# CPU_PHY.net
KiCad netlist of a schematic drawn in Altium Designer
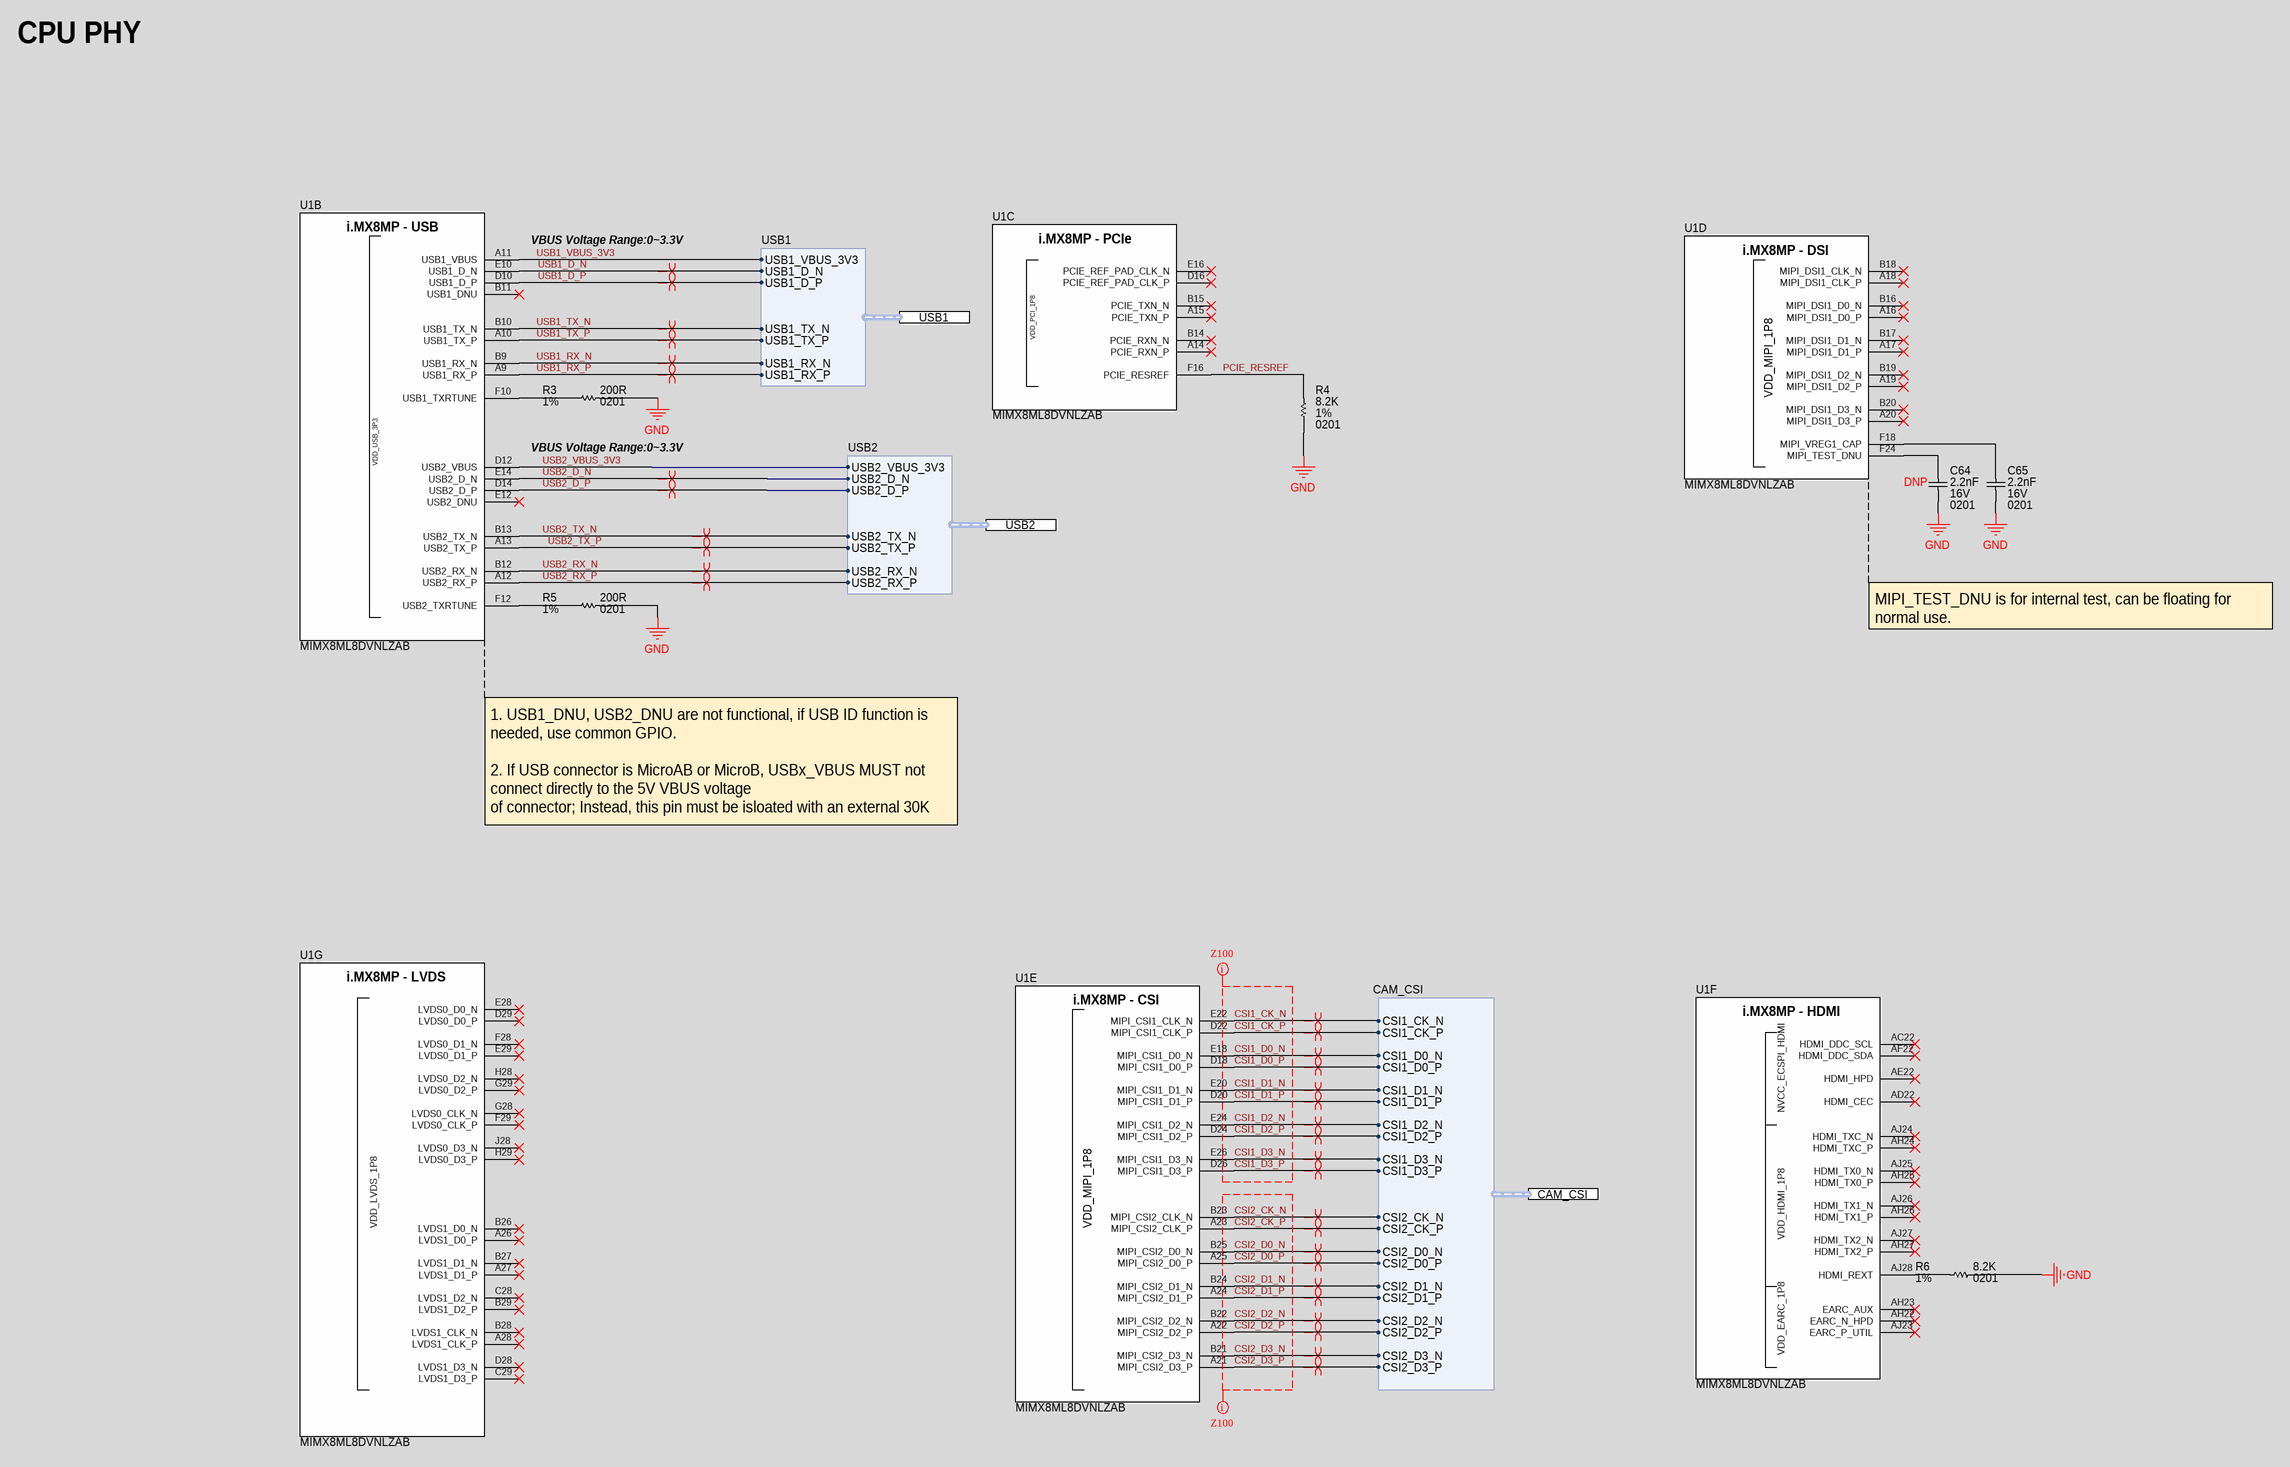
[diagram p0: CPU PHY.SchDoc]

(export (version "E")
  (design (tool "Eeschema 10.0.6"))
  (components
    (comp (ref "C64")
      (value "GRM033R71C222KA88D")
      (footprint "CAP_0201_CAPC0603X03N")
      (description "Multilayer Ceramic Capacitor, 2200 pF, 16 V, ± 10%, X7R, 0201 [0603 Metric]")
      (fields
        (field (name "MANUFACTURER") "Murata")
        (field (name "TOLERANCE") "10%")
        (field (name "VOLTAGE RATING") "16V")
        (field (name "CAPACITANCE") "2.2nF")
        (field (name "CASE/PACKAGE") "0201")
      )
      (libsource (lib "Electronic Devices_LIB") (part "CAP_2200pF_16V_X7R_0201"))
    )
    (comp (ref "C65")
      (value "GRM033R71C222KA88D")
      (footprint "CAP_0201_CAPC0603X03N")
      (description "Multilayer Ceramic Capacitor, 2200 pF, 16 V, ± 10%, X7R, 0201 [0603 Metric]")
      (fields
        (field (name "MANUFACTURER") "Murata")
        (field (name "TOLERANCE") "10%")
        (field (name "VOLTAGE RATING") "16V")
        (field (name "CAPACITANCE") "2.2nF")
        (field (name "CASE/PACKAGE") "0201")
      )
      (libsource (lib "Electronic Devices_LIB") (part "CAP_2200pF_16V_X7R_0201"))
    )
    (comp (ref "R3")
      (value "RC0201FR-07200RL")
      (footprint "RES_0201_RESC0603X02N")
      (description "SMD Chip Resistor, 200 Ohm, ± 1%, 50 mW, 0201 [0603 Metric], Thick Film, General Purpose")
      (fields
        (field (name "MANUFACTURER") "Yageo")
        (field (name "TOLERANCE") "1%")
        (field (name "RESISTANCE") "200R")
        (field (name "CASE/PACKAGE") "0201")
      )
      (libsource (lib "Electronic Devices_LIB") (part "RES_200R_1%_50mW_0201"))
    )
    (comp (ref "R4")
      (value "RC0201FR-078K2L")
      (footprint "RES_0201_RESC0603X02N")
      (description "Res Thick Film 0201 8.2K Ohm 1% 1/20W ±200ppm/°C Molded SMD Paper T/R")
      (fields
        (field (name "MANUFACTURER") "Yageo")
        (field (name "TOLERANCE") "1%")
        (field (name "RESISTANCE") "8.2K")
        (field (name "CASE/PACKAGE") "0201")
      )
      (libsource (lib "Electronic Devices_LIB") (part "RES_8.2K_1%_50mW_0201"))
    )
    (comp (ref "R5")
      (value "RC0201FR-07200RL")
      (footprint "RES_0201_RESC0603X02N")
      (description "SMD Chip Resistor, 200 Ohm, ± 1%, 50 mW, 0201 [0603 Metric], Thick Film, General Purpose")
      (fields
        (field (name "MANUFACTURER") "Yageo")
        (field (name "TOLERANCE") "1%")
        (field (name "RESISTANCE") "200R")
        (field (name "CASE/PACKAGE") "0201")
      )
      (libsource (lib "Electronic Devices_LIB") (part "RES_200R_1%_50mW_0201"))
    )
    (comp (ref "R6")
      (value "RC0201FR-078K2L")
      (footprint "RES_0201_RESC0603X02N")
      (description "Res Thick Film 0201 8.2K Ohm 1% 1/20W ±200ppm/°C Molded SMD Paper T/R")
      (fields
        (field (name "MANUFACTURER") "Yageo")
        (field (name "TOLERANCE") "1%")
        (field (name "RESISTANCE") "8.2K")
        (field (name "CASE/PACKAGE") "0201")
      )
      (libsource (lib "Electronic Devices_LIB") (part "RES_8.2K_1%_50mW_0201"))
    )
    (comp (ref "U1")
      (value "MIMX8ML8DVNLZAB")
      (footprint "IC_MPU_BGA548C50P29X29_1500X1500X148")
      (description "i.MX 8M Plus, Consumer, / TRAY TRAY MULTIPLE DP BAKEABLE RoHS Compliant: Yes")
      (fields (field (name "MANUFACTURER") "NXP Semiconductors"))
      (libsource (lib "Electronic Devices_LIB") (part "IC_MPU_8M_PLUS_MIMX8ML8DVNLZAB"))
    )
  )
  (nets
    (net (code "4") (name "/CSI1_CK_N") (class "Default")
      (node (ref "U1") (pin "E22") (pinfunction "MIPI_CSI1_CLK_N_E22") (pintype "passive"))
    )
    (net (code "5") (name "/CSI1_CK_P") (class "Default")
      (node (ref "U1") (pin "D22") (pinfunction "MIPI_CSI1_CLK_P_D22") (pintype "passive"))
    )
    (net (code "6") (name "/CSI1_D0_N") (class "Default")
      (node (ref "U1") (pin "E18") (pinfunction "MIPI_CSI1_D0_N_E18") (pintype "passive"))
    )
    (net (code "7") (name "/CSI1_D0_P") (class "Default")
      (node (ref "U1") (pin "D18") (pinfunction "MIPI_CSI1_D0_P_D18") (pintype "passive"))
    )
    (net (code "8") (name "/CSI1_D1_N") (class "Default")
      (node (ref "U1") (pin "E20") (pinfunction "MIPI_CSI1_D1_N_E20") (pintype "passive"))
    )
    (net (code "9") (name "/CSI1_D1_P") (class "Default")
      (node (ref "U1") (pin "D20") (pinfunction "MIPI_CSI1_D1_P_D20") (pintype "passive"))
    )
    (net (code "10") (name "/CSI1_D2_N") (class "Default")
      (node (ref "U1") (pin "E24") (pinfunction "MIPI_CSI1_D2_N_E24") (pintype "passive"))
    )
    (net (code "11") (name "/CSI1_D2_P") (class "Default")
      (node (ref "U1") (pin "D24") (pinfunction "MIPI_CSI1_D2_P_D24") (pintype "passive"))
    )
    (net (code "12") (name "/CSI1_D3_N") (class "Default")
      (node (ref "U1") (pin "E26") (pinfunction "MIPI_CSI1_D3_N_E26") (pintype "passive"))
    )
    (net (code "13") (name "/CSI1_D3_P") (class "Default")
      (node (ref "U1") (pin "D26") (pinfunction "MIPI_CSI1_D3_P_D26") (pintype "passive"))
    )
    (net (code "14") (name "/CSI2_CK_N") (class "Default")
      (node (ref "U1") (pin "B23") (pinfunction "MIPI_CSI2_CLK_N_B23") (pintype "passive"))
    )
    (net (code "15") (name "/CSI2_CK_P") (class "Default")
      (node (ref "U1") (pin "A23") (pinfunction "MIPI_CSI2_CLK_P_A23") (pintype "passive"))
    )
    (net (code "16") (name "/CSI2_D0_N") (class "Default")
      (node (ref "U1") (pin "B25") (pinfunction "MIPI_CSI2_D0_N_B25") (pintype "passive"))
    )
    (net (code "17") (name "/CSI2_D0_P") (class "Default")
      (node (ref "U1") (pin "A25") (pinfunction "MIPI_CSI2_D0_P_A25") (pintype "passive"))
    )
    (net (code "18") (name "/CSI2_D1_N") (class "Default")
      (node (ref "U1") (pin "B24") (pinfunction "MIPI_CSI2_D1_N_B24") (pintype "passive"))
    )
    (net (code "19") (name "/CSI2_D1_P") (class "Default")
      (node (ref "U1") (pin "A24") (pinfunction "MIPI_CSI2_D1_P_A24") (pintype "passive"))
    )
    (net (code "20") (name "/CSI2_D2_N") (class "Default")
      (node (ref "U1") (pin "B22") (pinfunction "MIPI_CSI2_D2_N_B22") (pintype "passive"))
    )
    (net (code "21") (name "/CSI2_D2_P") (class "Default")
      (node (ref "U1") (pin "A22") (pinfunction "MIPI_CSI2_D2_P_A22") (pintype "passive"))
    )
    (net (code "22") (name "/CSI2_D3_N") (class "Default")
      (node (ref "U1") (pin "B21") (pinfunction "MIPI_CSI2_D3_N_B21") (pintype "passive"))
    )
    (net (code "23") (name "/CSI2_D3_P") (class "Default")
      (node (ref "U1") (pin "A21") (pinfunction "MIPI_CSI2_D3_P_A21") (pintype "passive"))
    )
    (net (code "24") (name "/PCIE_RESREF") (class "Default")
      (node (ref "R4") (pin "2") (pinfunction "2_2") (pintype "passive"))
      (node (ref "U1") (pin "F16") (pinfunction "PCIE_RESREF_F16") (pintype "passive"))
    )
    (net (code "25") (name "/USB1_D_N") (class "Default")
      (node (ref "U1") (pin "E10") (pinfunction "USB1_D_N_E10") (pintype "passive"))
    )
    (net (code "26") (name "/USB1_D_P") (class "Default")
      (node (ref "U1") (pin "D10") (pinfunction "USB1_D_P_D10") (pintype "passive"))
    )
    (net (code "27") (name "/USB1_RX_N") (class "Default")
      (node (ref "U1") (pin "B9") (pinfunction "USB1_RX_N_B9") (pintype "passive"))
    )
    (net (code "28") (name "/USB1_RX_P") (class "Default")
      (node (ref "U1") (pin "A9") (pinfunction "USB1_RX_P_A9") (pintype "passive"))
    )
    (net (code "29") (name "/USB1_TX_N") (class "Default")
      (node (ref "U1") (pin "B10") (pinfunction "USB1_TX_N_B10") (pintype "passive"))
    )
    (net (code "30") (name "/USB1_TX_P") (class "Default")
      (node (ref "U1") (pin "A10") (pinfunction "USB1_TX_P_A10") (pintype "passive"))
    )
    (net (code "31") (name "/USB1_VBUS_3V3") (class "Default")
      (node (ref "U1") (pin "A11") (pinfunction "USB1_VBUS_A11") (pintype "passive"))
    )
    (net (code "32") (name "/USB2_D_N") (class "Default")
      (node (ref "U1") (pin "E14") (pinfunction "USB2_D_N_E14") (pintype "passive"))
    )
    (net (code "33") (name "/USB2_D_P") (class "Default")
      (node (ref "U1") (pin "D14") (pinfunction "USB2_D_P_D14") (pintype "passive"))
    )
    (net (code "34") (name "/USB2_RX_N") (class "Default")
      (node (ref "U1") (pin "B12") (pinfunction "USB2_RX_N_B12") (pintype "passive"))
    )
    (net (code "35") (name "/USB2_RX_P") (class "Default")
      (node (ref "U1") (pin "A12") (pinfunction "USB2_RX_P_A12") (pintype "passive"))
    )
    (net (code "36") (name "/USB2_TX_N") (class "Default")
      (node (ref "U1") (pin "B13") (pinfunction "USB2_TX_N_B13") (pintype "passive"))
    )
    (net (code "37") (name "/USB2_TX_P") (class "Default")
      (node (ref "U1") (pin "A13") (pinfunction "USB2_TX_P_A13") (pintype "passive"))
    )
    (net (code "38") (name "/USB2_VBUS_3V3") (class "Default")
      (node (ref "U1") (pin "D12") (pinfunction "USB2_VBUS_D12") (pintype "passive"))
    )
    (net (code "42") (name "GND") (class "Default")
      (node (ref "C64") (pin "1") (pinfunction "1_1") (pintype "passive"))
      (node (ref "C65") (pin "1") (pinfunction "1_1") (pintype "passive"))
      (node (ref "R3") (pin "2") (pinfunction "2_2") (pintype "passive"))
      (node (ref "R4") (pin "1") (pinfunction "1_1") (pintype "passive"))
      (node (ref "R5") (pin "2") (pinfunction "2_2") (pintype "passive"))
      (node (ref "R6") (pin "1") (pinfunction "1_1") (pintype "passive"))
    )
    (net (code "43") (name "Net-(U1B-USB1_TXRTUNE)") (class "Default")
      (node (ref "R3") (pin "1") (pinfunction "1_1") (pintype "passive"))
      (node (ref "U1") (pin "F10") (pinfunction "USB1_TXRTUNE_F10") (pintype "passive"))
    )
    (net (code "44") (name "Net-(U1B-USB2_TXRTUNE)") (class "Default")
      (node (ref "R5") (pin "1") (pinfunction "1_1") (pintype "passive"))
      (node (ref "U1") (pin "F12") (pinfunction "USB2_TXRTUNE_F12") (pintype "passive"))
    )
    (net (code "45") (name "Net-(U1D-MIPI_TEST_DNU)") (class "Default")
      (node (ref "C64") (pin "2") (pinfunction "2_2") (pintype "passive"))
      (node (ref "U1") (pin "F24") (pinfunction "MIPI_TEST_DNU_F24") (pintype "passive"))
    )
    (net (code "46") (name "Net-(U1D-MIPI_VREG1_CAP)") (class "Default")
      (node (ref "C65") (pin "2") (pinfunction "2_2") (pintype "passive"))
      (node (ref "U1") (pin "F18") (pinfunction "MIPI_VREG1_CAP_F18") (pintype "passive"))
    )
    (net (code "47") (name "Net-(U1F-HDMI_REXT)") (class "Default")
      (node (ref "R6") (pin "2") (pinfunction "2_2") (pintype "passive"))
      (node (ref "U1") (pin "AJ28") (pinfunction "HDMI_REXT_AJ28") (pintype "passive"))
    )
    (net (code "48") (name "unconnected-(U1B-USB1_DNU-PadB11)") (class "Default")
      (node (ref "U1") (pin "B11") (pinfunction "USB1_DNU_B11") (pintype "passive+no_connect"))
    )
    (net (code "49") (name "unconnected-(U1B-USB2_DNU-PadE12)") (class "Default")
      (node (ref "U1") (pin "E12") (pinfunction "USB2_DNU_E12") (pintype "passive+no_connect"))
    )
    (net (code "50") (name "unconnected-(U1C-PCIE_REF_PAD_CLK_N-PadE16)") (class "Default")
      (node (ref "U1") (pin "E16") (pinfunction "PCIE_REF_PAD_CLK_N_E16") (pintype "passive+no_connect"))
    )
    (net (code "51") (name "unconnected-(U1C-PCIE_REF_PAD_CLK_P-PadD16)") (class "Default")
      (node (ref "U1") (pin "D16") (pinfunction "PCIE_REF_PAD_CLK_P_D16") (pintype "passive+no_connect"))
    )
    (net (code "52") (name "unconnected-(U1C-PCIE_RXN_N-PadB14)") (class "Default")
      (node (ref "U1") (pin "B14") (pinfunction "PCIE_RXN_N_B14") (pintype "passive+no_connect"))
    )
    (net (code "53") (name "unconnected-(U1C-PCIE_RXN_P-PadA14)") (class "Default")
      (node (ref "U1") (pin "A14") (pinfunction "PCIE_RXN_P_A14") (pintype "passive+no_connect"))
    )
    (net (code "54") (name "unconnected-(U1C-PCIE_TXN_N-PadB15)") (class "Default")
      (node (ref "U1") (pin "B15") (pinfunction "PCIE_TXN_N_B15") (pintype "passive+no_connect"))
    )
    (net (code "55") (name "unconnected-(U1C-PCIE_TXN_P-PadA15)") (class "Default")
      (node (ref "U1") (pin "A15") (pinfunction "PCIE_TXN_P_A15") (pintype "passive+no_connect"))
    )
    (net (code "56") (name "unconnected-(U1D-MIPI_DSI1_CLK_N-PadB18)") (class "Default")
      (node (ref "U1") (pin "B18") (pinfunction "MIPI_DSI1_CLK_N_B18") (pintype "passive+no_connect"))
    )
    (net (code "57") (name "unconnected-(U1D-MIPI_DSI1_CLK_P-PadA18)") (class "Default")
      (node (ref "U1") (pin "A18") (pinfunction "MIPI_DSI1_CLK_P_A18") (pintype "passive+no_connect"))
    )
    (net (code "58") (name "unconnected-(U1D-MIPI_DSI1_D0_N-PadB16)") (class "Default")
      (node (ref "U1") (pin "B16") (pinfunction "MIPI_DSI1_D0_N_B16") (pintype "passive+no_connect"))
    )
    (net (code "59") (name "unconnected-(U1D-MIPI_DSI1_D0_P-PadA16)") (class "Default")
      (node (ref "U1") (pin "A16") (pinfunction "MIPI_DSI1_D0_P_A16") (pintype "passive+no_connect"))
    )
    (net (code "60") (name "unconnected-(U1D-MIPI_DSI1_D1_N-PadB17)") (class "Default")
      (node (ref "U1") (pin "B17") (pinfunction "MIPI_DSI1_D1_N_B17") (pintype "passive+no_connect"))
    )
    (net (code "61") (name "unconnected-(U1D-MIPI_DSI1_D1_P-PadA17)") (class "Default")
      (node (ref "U1") (pin "A17") (pinfunction "MIPI_DSI1_D1_P_A17") (pintype "passive+no_connect"))
    )
    (net (code "62") (name "unconnected-(U1D-MIPI_DSI1_D2_N-PadB19)") (class "Default")
      (node (ref "U1") (pin "B19") (pinfunction "MIPI_DSI1_D2_N_B19") (pintype "passive+no_connect"))
    )
    (net (code "63") (name "unconnected-(U1D-MIPI_DSI1_D2_P-PadA19)") (class "Default")
      (node (ref "U1") (pin "A19") (pinfunction "MIPI_DSI1_D2_P_A19") (pintype "passive+no_connect"))
    )
    (net (code "64") (name "unconnected-(U1D-MIPI_DSI1_D3_N-PadB20)") (class "Default")
      (node (ref "U1") (pin "B20") (pinfunction "MIPI_DSI1_D3_N_B20") (pintype "passive+no_connect"))
    )
    (net (code "65") (name "unconnected-(U1D-MIPI_DSI1_D3_P-PadA20)") (class "Default")
      (node (ref "U1") (pin "A20") (pinfunction "MIPI_DSI1_D3_P_A20") (pintype "passive+no_connect"))
    )
    (net (code "66") (name "unconnected-(U1F-EARC_AUX-PadAH23)") (class "Default")
      (node (ref "U1") (pin "AH23") (pinfunction "EARC_AUX_AH23") (pintype "passive+no_connect"))
    )
    (net (code "67") (name "unconnected-(U1F-EARC_N_HPD-PadAH22)") (class "Default")
      (node (ref "U1") (pin "AH22") (pinfunction "EARC_N_HPD_AH22") (pintype "passive+no_connect"))
    )
    (net (code "68") (name "unconnected-(U1F-EARC_P_UTIL-PadAJ23)") (class "Default")
      (node (ref "U1") (pin "AJ23") (pinfunction "EARC_P_UTIL_AJ23") (pintype "passive+no_connect"))
    )
    (net (code "69") (name "unconnected-(U1F-HDMI_CEC-PadAD22)") (class "Default")
      (node (ref "U1") (pin "AD22") (pinfunction "HDMI_CEC_AD22") (pintype "passive+no_connect"))
    )
    (net (code "70") (name "unconnected-(U1F-HDMI_DDC_SCL-PadAC22)") (class "Default")
      (node (ref "U1") (pin "AC22") (pinfunction "HDMI_DDC_SCL_AC22") (pintype "passive+no_connect"))
    )
    (net (code "71") (name "unconnected-(U1F-HDMI_DDC_SDA-PadAF22)") (class "Default")
      (node (ref "U1") (pin "AF22") (pinfunction "HDMI_DDC_SDA_AF22") (pintype "passive+no_connect"))
    )
    (net (code "72") (name "unconnected-(U1F-HDMI_HPD-PadAE22)") (class "Default")
      (node (ref "U1") (pin "AE22") (pinfunction "HDMI_HPD_AE22") (pintype "passive+no_connect"))
    )
    (net (code "73") (name "unconnected-(U1F-HDMI_TX0_N-PadAJ25)") (class "Default")
      (node (ref "U1") (pin "AJ25") (pinfunction "HDMI_TX0_N_AJ25") (pintype "passive+no_connect"))
    )
    (net (code "74") (name "unconnected-(U1F-HDMI_TX0_P-PadAH25)") (class "Default")
      (node (ref "U1") (pin "AH25") (pinfunction "HDMI_TX0_P_AH25") (pintype "passive+no_connect"))
    )
    (net (code "75") (name "unconnected-(U1F-HDMI_TX1_N-PadAJ26)") (class "Default")
      (node (ref "U1") (pin "AJ26") (pinfunction "HDMI_TX1_N_AJ26") (pintype "passive+no_connect"))
    )
    (net (code "76") (name "unconnected-(U1F-HDMI_TX1_P-PadAH26)") (class "Default")
      (node (ref "U1") (pin "AH26") (pinfunction "HDMI_TX1_P_AH26") (pintype "passive+no_connect"))
    )
    (net (code "77") (name "unconnected-(U1F-HDMI_TX2_N-PadAJ27)") (class "Default")
      (node (ref "U1") (pin "AJ27") (pinfunction "HDMI_TX2_N_AJ27") (pintype "passive+no_connect"))
    )
    (net (code "78") (name "unconnected-(U1F-HDMI_TX2_P-PadAH27)") (class "Default")
      (node (ref "U1") (pin "AH27") (pinfunction "HDMI_TX2_P_AH27") (pintype "passive+no_connect"))
    )
    (net (code "79") (name "unconnected-(U1F-HDMI_TXC_N-PadAJ24)") (class "Default")
      (node (ref "U1") (pin "AJ24") (pinfunction "HDMI_TXC_N_AJ24") (pintype "passive+no_connect"))
    )
    (net (code "80") (name "unconnected-(U1F-HDMI_TXC_P-PadAH24)") (class "Default")
      (node (ref "U1") (pin "AH24") (pinfunction "HDMI_TXC_P_AH24") (pintype "passive+no_connect"))
    )
    (net (code "81") (name "unconnected-(U1G-LVDS0_CLK_N-PadG28)") (class "Default")
      (node (ref "U1") (pin "G28") (pinfunction "LVDS0_CLK_N_G28") (pintype "passive+no_connect"))
    )
    (net (code "82") (name "unconnected-(U1G-LVDS0_CLK_P-PadF29)") (class "Default")
      (node (ref "U1") (pin "F29") (pinfunction "LVDS0_CLK_P_F29") (pintype "passive+no_connect"))
    )
    (net (code "83") (name "unconnected-(U1G-LVDS0_D0_N-PadE28)") (class "Default")
      (node (ref "U1") (pin "E28") (pinfunction "LVDS0_D0_N_E28") (pintype "passive+no_connect"))
    )
    (net (code "84") (name "unconnected-(U1G-LVDS0_D0_P-PadD29)") (class "Default")
      (node (ref "U1") (pin "D29") (pinfunction "LVDS0_D0_P_D29") (pintype "passive+no_connect"))
    )
    (net (code "85") (name "unconnected-(U1G-LVDS0_D1_N-PadF28)") (class "Default")
      (node (ref "U1") (pin "F28") (pinfunction "LVDS0_D1_N_F28") (pintype "passive+no_connect"))
    )
    (net (code "86") (name "unconnected-(U1G-LVDS0_D1_P-PadE29)") (class "Default")
      (node (ref "U1") (pin "E29") (pinfunction "LVDS0_D1_P_E29") (pintype "passive+no_connect"))
    )
    (net (code "87") (name "unconnected-(U1G-LVDS0_D2_N-PadH28)") (class "Default")
      (node (ref "U1") (pin "H28") (pinfunction "LVDS0_D2_N_H28") (pintype "passive+no_connect"))
    )
    (net (code "88") (name "unconnected-(U1G-LVDS0_D2_P-PadG29)") (class "Default")
      (node (ref "U1") (pin "G29") (pinfunction "LVDS0_D2_P_G29") (pintype "passive+no_connect"))
    )
    (net (code "89") (name "unconnected-(U1G-LVDS0_D3_N-PadJ28)") (class "Default")
      (node (ref "U1") (pin "J28") (pinfunction "LVDS0_D3_N_J28") (pintype "passive+no_connect"))
    )
    (net (code "90") (name "unconnected-(U1G-LVDS0_D3_P-PadH29)") (class "Default")
      (node (ref "U1") (pin "H29") (pinfunction "LVDS0_D3_P_H29") (pintype "passive+no_connect"))
    )
    (net (code "91") (name "unconnected-(U1G-LVDS1_CLK_N-PadB28)") (class "Default")
      (node (ref "U1") (pin "B28") (pinfunction "LVDS1_CLK_N_B28") (pintype "passive+no_connect"))
    )
    (net (code "92") (name "unconnected-(U1G-LVDS1_CLK_P-PadA28)") (class "Default")
      (node (ref "U1") (pin "A28") (pinfunction "LVDS1_CLK_P_A28") (pintype "passive+no_connect"))
    )
    (net (code "93") (name "unconnected-(U1G-LVDS1_D0_N-PadB26)") (class "Default")
      (node (ref "U1") (pin "B26") (pinfunction "LVDS1_D0_N_B26") (pintype "passive+no_connect"))
    )
    (net (code "94") (name "unconnected-(U1G-LVDS1_D0_P-PadA26)") (class "Default")
      (node (ref "U1") (pin "A26") (pinfunction "LVDS1_D0_P_A26") (pintype "passive+no_connect"))
    )
    (net (code "95") (name "unconnected-(U1G-LVDS1_D1_N-PadB27)") (class "Default")
      (node (ref "U1") (pin "B27") (pinfunction "LVDS1_D1_N_B27") (pintype "passive+no_connect"))
    )
    (net (code "96") (name "unconnected-(U1G-LVDS1_D1_P-PadA27)") (class "Default")
      (node (ref "U1") (pin "A27") (pinfunction "LVDS1_D1_P_A27") (pintype "passive+no_connect"))
    )
    (net (code "97") (name "unconnected-(U1G-LVDS1_D2_N-PadC28)") (class "Default")
      (node (ref "U1") (pin "C28") (pinfunction "LVDS1_D2_N_C28") (pintype "passive+no_connect"))
    )
    (net (code "98") (name "unconnected-(U1G-LVDS1_D2_P-PadB29)") (class "Default")
      (node (ref "U1") (pin "B29") (pinfunction "LVDS1_D2_P_B29") (pintype "passive+no_connect"))
    )
    (net (code "99") (name "unconnected-(U1G-LVDS1_D3_N-PadD28)") (class "Default")
      (node (ref "U1") (pin "D28") (pinfunction "LVDS1_D3_N_D28") (pintype "passive+no_connect"))
    )
    (net (code "100") (name "unconnected-(U1G-LVDS1_D3_P-PadC29)") (class "Default")
      (node (ref "U1") (pin "C29") (pinfunction "LVDS1_D3_P_C29") (pintype "passive+no_connect"))
    )
  )
)
